# DPS368_SensorBreakout.net
KiCad netlist of a schematic drawn in EAGLE
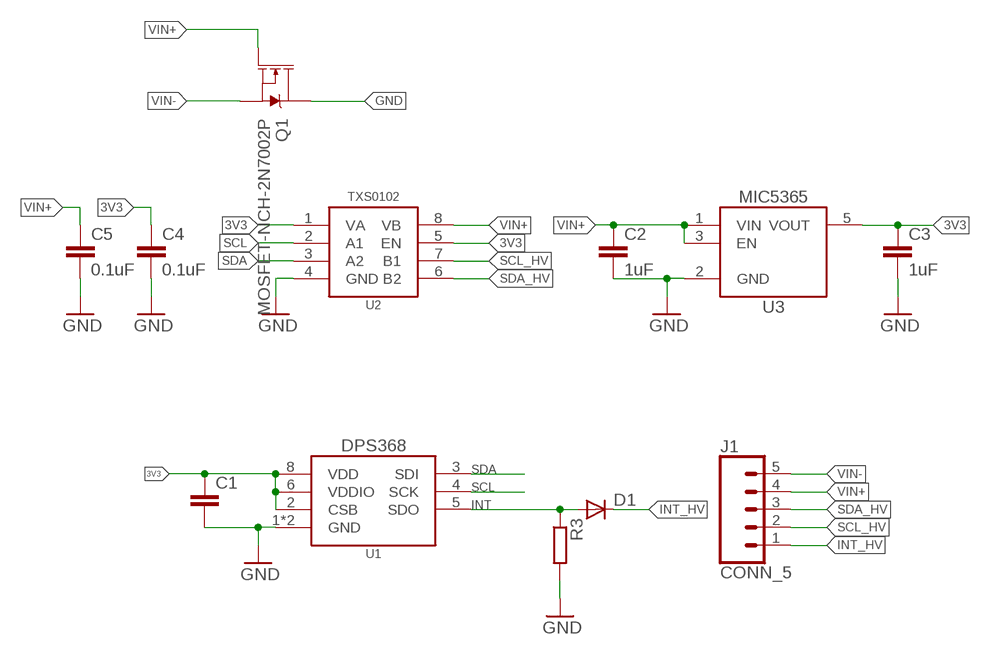
[diagram p0: schematic, sheet 1]

(export (version "E")
  (design (tool "Eeschema 10.0.6"))
  (components
    (comp (ref "C1")
      (value "C-EU0.1UFC0603")
      (footprint "eagle-import:C0603")
      (fields (field (name "MF") "Murata") (field (name "MPN") "GCM188R71E104KA57D"))
      (libsource (lib "eagle-import") (part "C-EUC06030.1UF"))
    )
    (comp (ref "C2")
      (value "1uF")
      (footprint "eagle-import:C0603")
      (fields (field (name "MF") "Murata") (field (name "MPN") "GRM188R61C105KA12D"))
      (libsource (lib "eagle-import") (part "C-EUC06031UF"))
    )
    (comp (ref "C3")
      (value "1uF")
      (footprint "eagle-import:C0603")
      (fields (field (name "MF") "Murata") (field (name "MPN") "GRM188R61C105KA12D"))
      (libsource (lib "eagle-import") (part "C-EUC06031UF"))
    )
    (comp (ref "C4")
      (value "0.1uF")
      (footprint "eagle-import:C0603")
      (fields (field (name "MF") "Murata") (field (name "MPN") "GCM188R71E104KA57D"))
      (libsource (lib "eagle-import") (part "C-EUC06030.1UF"))
    )
    (comp (ref "C5")
      (value "0.1uF")
      (footprint "eagle-import:C0603")
      (fields (field (name "MF") "Murata") (field (name "MPN") "GCM188R71E104KA57D"))
      (libsource (lib "eagle-import") (part "C-EUC06030.1UF"))
    )
    (comp (ref "D1")
      (value "DIODESOD-323")
      (footprint "eagle-import:SOD323-R")
      (libsource (lib "eagle-import") (part "DIODESOD-323"))
    )
    (comp (ref "J1")
      (value "CONN_5")
      (footprint "eagle-import:1X05")
      (fields (field (name "MF") "On Shore") (field (name "MPN") "OSTVN05A150"))
      (libsource (lib "eagle-import") (part "CONN_5"))
    )
    (comp (ref "Q1")
      (value "MOSFET-NCH-2N7002P")
      (footprint "eagle-import:SOT23-3")
      (fields (field (name "MF") "Nexperia") (field (name "MPN") "2N7002P,215"))
      (libsource (lib "eagle-import") (part "MOSFET-NCH-2N7002P"))
    )
    (comp (ref "R3")
      (value "R-EU_100KR0603")
      (footprint "eagle-import:R0603")
      (fields
        (field (name "MF") "Yageo")
        (field (name "MPN") "RC0603FR-07100KL")
        (field (name "VALUE_PART") "100k")
      )
      (libsource (lib "eagle-import") (part "R-EU_R0603100K"))
    )
    (comp (ref "U1")
      (value "DPS368")
      (footprint "eagle-import:PG-VLGA-8")
      (fields
        (field (name "DISP") "DPS368")
        (field (name "MF") "Infineon")
        (field (name "MPN") "DPS368XTSA1")
      )
      (libsource (lib "eagle-import") (part "DPS368"))
    )
    (comp (ref "U2")
      (value "TXS0102DQM")
      (footprint "eagle-import:DQM_R-PX2SON-N8")
      (fields (field (name "MF") "TI") (field (name "MPN") "TXS0102DQMR"))
      (libsource (lib "eagle-import") (part "TXS0102DQM"))
    )
    (comp (ref "U3")
      (value "MIC53653.3SC70")
      (footprint "eagle-import:DCK_R-PDSO-G5")
      (fields (field (name "MF") "Microchip") (field (name "MPN") "MIC5365-3.3YC5-TR"))
      (libsource (lib "eagle-import") (part "MIC5365SC703.3"))
    )
  )
  (nets
    (net (code "1") (name "/INT") (class "Default")
      (node (ref "D1") (pin "A") (pinfunction "A_A") (pintype "passive"))
      (node (ref "R3") (pin "1") (pinfunction "1_1") (pintype "passive"))
      (node (ref "U1") (pin "5") (pinfunction "SDO_5") (pintype "bidirectional"))
    )
    (net (code "2") (name "3V3") (class "Default")
      (node (ref "C1") (pin "1") (pinfunction "1_1") (pintype "passive"))
      (node (ref "C3") (pin "1") (pinfunction "1_1") (pintype "passive"))
      (node (ref "C4") (pin "1") (pinfunction "1_1") (pintype "passive"))
      (node (ref "U1") (pin "2") (pinfunction "CSB_2") (pintype "bidirectional"))
      (node (ref "U1") (pin "6") (pinfunction "VDDIO_6") (pintype "bidirectional"))
      (node (ref "U1") (pin "8") (pinfunction "VDD_8") (pintype "power_in"))
      (node (ref "U2") (pin "1") (pinfunction "VA_1") (pintype "power_in"))
      (node (ref "U2") (pin "5") (pinfunction "EN_5") (pintype "input"))
      (node (ref "U3") (pin "5") (pinfunction "VOUT_5") (pintype "power_in"))
    )
    (net (code "3") (name "GND") (class "Default")
      (node (ref "C1") (pin "2") (pinfunction "2_2") (pintype "passive"))
      (node (ref "C2") (pin "2") (pinfunction "2_2") (pintype "passive"))
      (node (ref "C3") (pin "2") (pinfunction "2_2") (pintype "passive"))
      (node (ref "C4") (pin "2") (pinfunction "2_2") (pintype "passive"))
      (node (ref "C5") (pin "2") (pinfunction "2_2") (pintype "passive"))
      (node (ref "Q1") (pin "3") (pinfunction "D_3") (pintype "bidirectional"))
      (node (ref "R3") (pin "2") (pinfunction "2_2") (pintype "passive"))
      (node (ref "U1") (pin "1") (pinfunction "GND_1") (pintype "power_in"))
      (node (ref "U1") (pin "7") (pinfunction "GND_7") (pintype "power_in"))
      (node (ref "U2") (pin "4") (pinfunction "GND_4") (pintype "power_in"))
      (node (ref "U3") (pin "2") (pinfunction "GND_2") (pintype "power_in"))
    )
    (net (code "4") (name "INT_HV") (class "Default")
      (node (ref "D1") (pin "C") (pinfunction "C_C") (pintype "passive"))
      (node (ref "J1") (pin "1") (pinfunction "1_1") (pintype "passive"))
    )
    (net (code "5") (name "SCL") (class "Default")
      (node (ref "U1") (pin "4") (pinfunction "SCK_4") (pintype "bidirectional"))
      (node (ref "U2") (pin "2") (pinfunction "A1_2") (pintype "bidirectional"))
    )
    (net (code "6") (name "SCL_HV") (class "Default")
      (node (ref "J1") (pin "2") (pinfunction "2_2") (pintype "passive"))
      (node (ref "U2") (pin "7") (pinfunction "B1_7") (pintype "bidirectional"))
    )
    (net (code "7") (name "SDA") (class "Default")
      (node (ref "U1") (pin "3") (pinfunction "SDI_3") (pintype "bidirectional"))
      (node (ref "U2") (pin "3") (pinfunction "A2_3") (pintype "bidirectional"))
    )
    (net (code "8") (name "SDA_HV") (class "Default")
      (node (ref "J1") (pin "3") (pinfunction "3_3") (pintype "passive"))
      (node (ref "U2") (pin "6") (pinfunction "B2_6") (pintype "bidirectional"))
    )
    (net (code "9") (name "VIN+") (class "Default")
      (node (ref "C2") (pin "1") (pinfunction "1_1") (pintype "passive"))
      (node (ref "C5") (pin "1") (pinfunction "1_1") (pintype "passive"))
      (node (ref "J1") (pin "4") (pinfunction "4_4") (pintype "passive"))
      (node (ref "Q1") (pin "1") (pinfunction "G_1") (pintype "bidirectional"))
      (node (ref "U2") (pin "8") (pinfunction "VB_8") (pintype "power_in"))
      (node (ref "U3") (pin "1") (pinfunction "VIN_1") (pintype "power_in"))
      (node (ref "U3") (pin "3") (pinfunction "EN_3") (pintype "input"))
    )
    (net (code "10") (name "VIN-") (class "Default")
      (node (ref "J1") (pin "5") (pinfunction "5_5") (pintype "passive"))
      (node (ref "Q1") (pin "2") (pinfunction "S_2") (pintype "bidirectional"))
    )
  )
)
